# X2C_DC_SHIELD_REVB.net
KiCad netlist of a schematic drawn in EAGLE
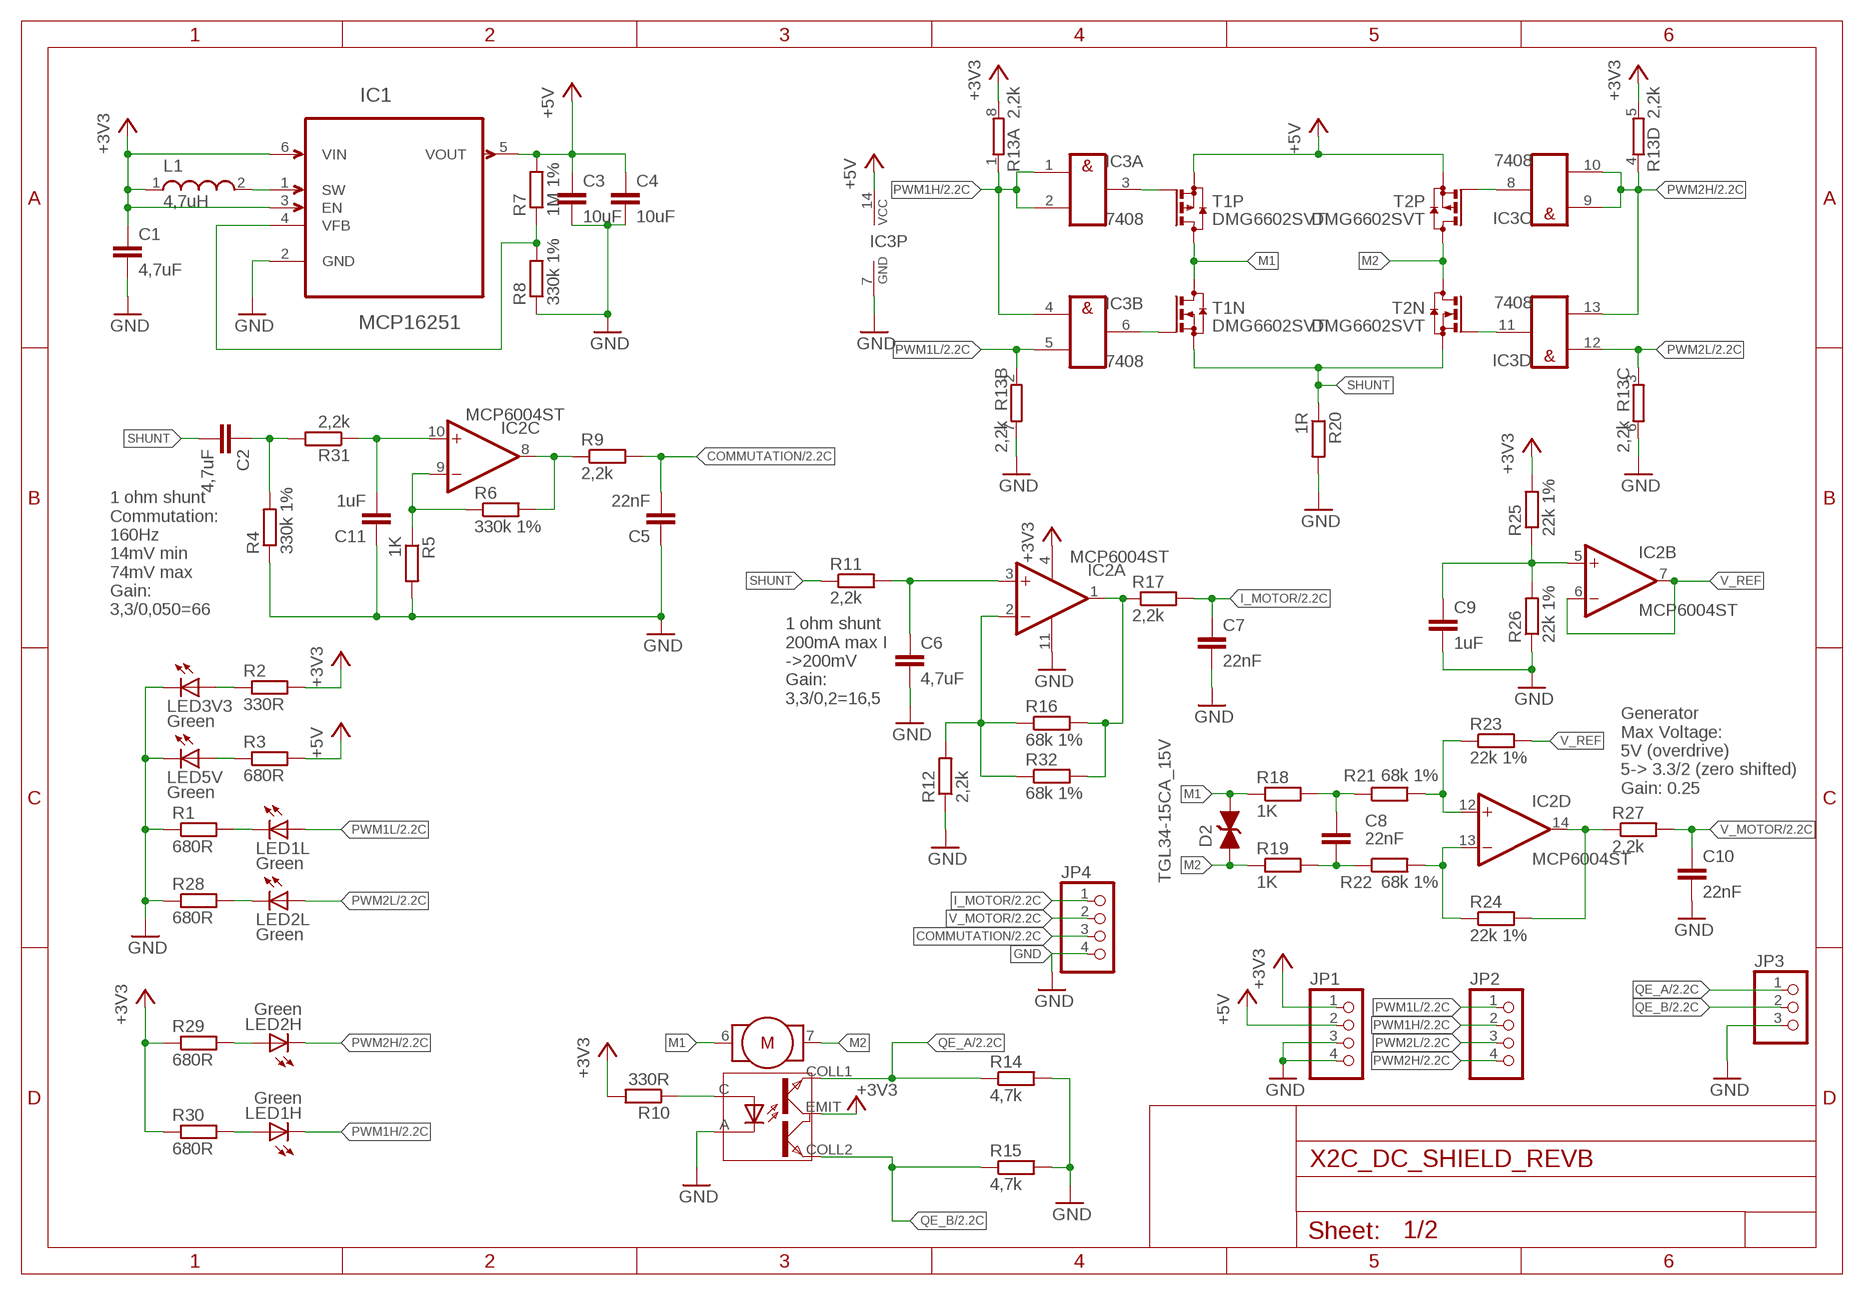
[diagram p0: schematic, sheet 1]
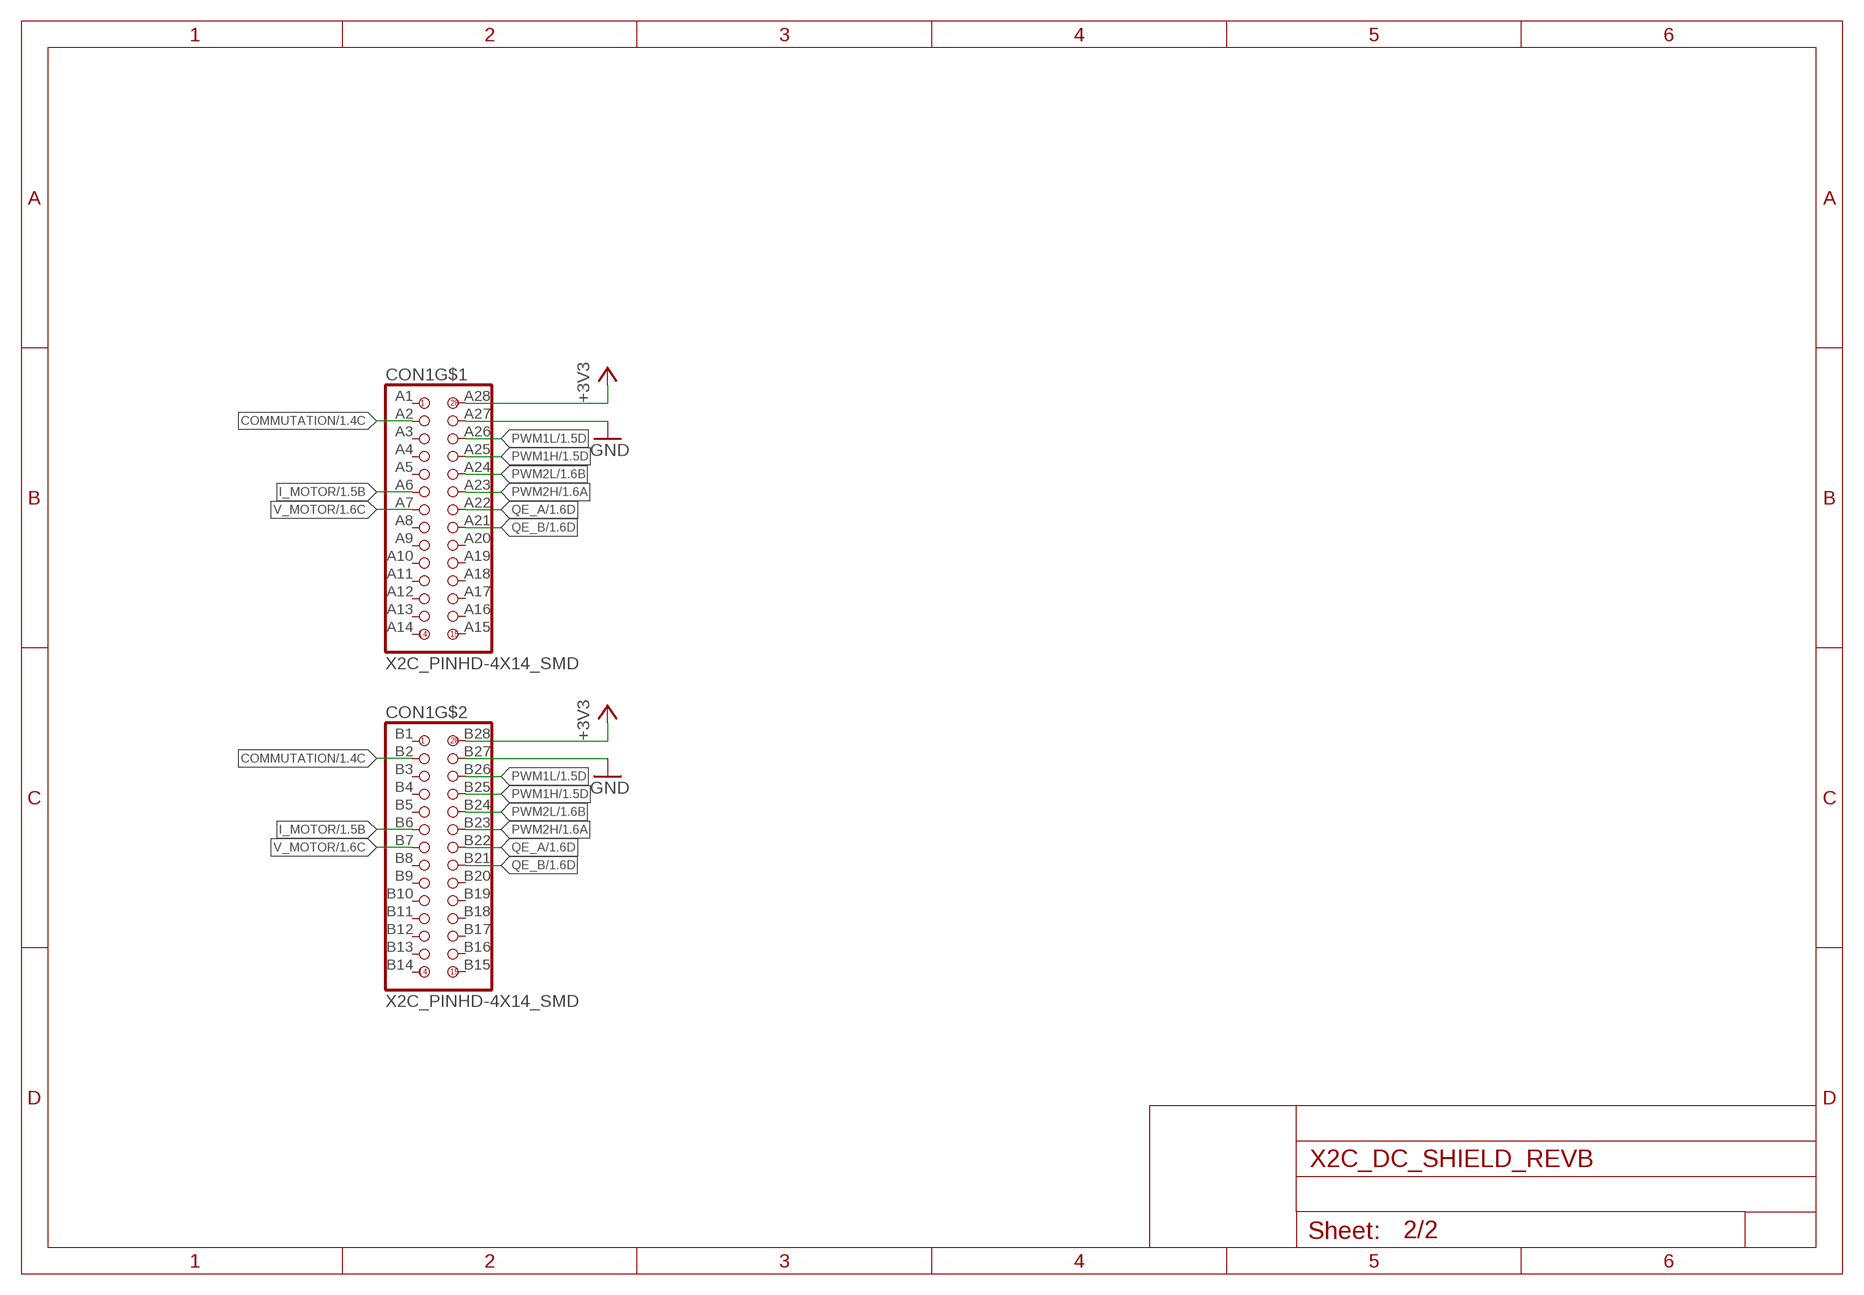
[diagram p1: schematic, sheet 2]

(export (version "E")
  (design (tool "Eeschema 10.0.6"))
  (components
    (comp (ref "C1")
      (value "4,7uF")
      (footprint "eagle-import:C0603K")
      (libsource (lib "eagle-import") (part "KANDO_KOZOS_C-EU-SMD_0603_4,7UF_16V"))
    )
    (comp (ref "C2")
      (value "4,7uF")
      (footprint "eagle-import:C0603K")
      (libsource (lib "eagle-import") (part "KANDO_KOZOS_C-EU-SMD_0603_4,7UF_16V"))
    )
    (comp (ref "C3")
      (value "10uF")
      (footprint "eagle-import:C0805K")
      (libsource (lib "eagle-import") (part "KANDO_KOZOS_C-EU-SMD_0805_10UF_16V"))
    )
    (comp (ref "C4")
      (value "10uF")
      (footprint "eagle-import:C0805K")
      (libsource (lib "eagle-import") (part "C-EU-SMD_0805_10UF_16V"))
    )
    (comp (ref "C5")
      (value "22nF")
      (footprint "eagle-import:C0603K")
      (libsource (lib "eagle-import") (part "C-EU-SMD_0603_22NF_16V"))
    )
    (comp (ref "C6")
      (value "4,7uF")
      (footprint "eagle-import:C0603K")
      (libsource (lib "eagle-import") (part "C-EU-SMD_0603_4,7UF_16V"))
    )
    (comp (ref "C7")
      (value "22nF")
      (footprint "eagle-import:C0603K")
      (libsource (lib "eagle-import") (part "C-EU-SMD_0603_22NF_16V"))
    )
    (comp (ref "C8")
      (value "22nF")
      (footprint "eagle-import:C0603K")
      (libsource (lib "eagle-import") (part "C-EU-SMD_0603_22NF_16V"))
    )
    (comp (ref "C9")
      (value "1uF")
      (footprint "eagle-import:C0603K")
      (libsource (lib "eagle-import") (part "C-EU-SMD_0603_1UF_10V"))
    )
    (comp (ref "C10")
      (value "22nF")
      (footprint "eagle-import:C0603K")
      (libsource (lib "eagle-import") (part "C-EU-SMD_0603_22NF_16V"))
    )
    (comp (ref "C11")
      (value "1uF")
      (footprint "eagle-import:C0603K")
      (libsource (lib "eagle-import") (part "KANDO_KOZOS_V2_C-EU-SMD_0603_1UF_10V"))
    )
    (comp (ref "D2")
      (value "TGL34-15CA_15V")
      (footprint "eagle-import:DO213AA")
      (libsource (lib "eagle-import") (part "TRANSIL_DUAL_DIODE"))
    )
    (comp (ref "IC1")
      (value "MCP16251")
      (footprint "eagle-import:SOT95P270X145-6N")
      (libsource (lib "eagle-import") (part "MCP16251"))
    )
    (comp (ref "IC2")
      (value "MCP6004ST")
      (footprint "eagle-import:TSSOP14")
      (libsource (lib "eagle-import") (part "MCP6004ST"))
    )
    (comp (ref "IC3")
      (value "7408")
      (footprint "eagle-import:TSSOP14")
      (libsource (lib "eagle-import") (part "7408"))
    )
    (comp (ref "JP1")
      (value "PINHD-1X4")
      (footprint "eagle-import:1X04")
      (libsource (lib "eagle-import") (part "PINHD-1X4"))
    )
    (comp (ref "JP2")
      (value "PINHD-1X4")
      (footprint "eagle-import:1X04")
      (libsource (lib "eagle-import") (part "PINHD-1X4"))
    )
    (comp (ref "JP3")
      (value "PINHD-1X03_2.54")
      (footprint "eagle-import:1X03")
      (libsource (lib "eagle-import") (part "PINHD-1X03_2.54"))
    )
    (comp (ref "JP4")
      (value "PINHD-1X4")
      (footprint "eagle-import:1X04")
      (libsource (lib "eagle-import") (part "PINHD-1X4"))
    )
    (comp (ref "L1")
      (value "4,7uH")
      (footprint "eagle-import:WE-TPC_3816")
      (libsource (lib "eagle-import") (part "WE-TPC_3816_4,7UH_0,9A"))
    )
    (comp (ref "LED1H")
      (value "Green")
      (footprint "eagle-import:CHIPLED_0805")
      (libsource (lib "eagle-import") (part "LEDCHIPLED_0805_GREEN"))
    )
    (comp (ref "LED1L")
      (value "Green")
      (footprint "eagle-import:CHIPLED_0805")
      (libsource (lib "eagle-import") (part "LEDCHIPLED_0805_GREEN"))
    )
    (comp (ref "LED2H")
      (value "Green")
      (footprint "eagle-import:CHIPLED_0805")
      (libsource (lib "eagle-import") (part "LEDCHIPLED_0805_GREEN"))
    )
    (comp (ref "LED2L")
      (value "Green")
      (footprint "eagle-import:CHIPLED_0805")
      (libsource (lib "eagle-import") (part "LEDCHIPLED_0805_GREEN"))
    )
    (comp (ref "LED3V3")
      (value "Green")
      (footprint "eagle-import:CHIPLED_0805")
      (libsource (lib "eagle-import") (part "LEDCHIPLED_0805_GREEN"))
    )
    (comp (ref "LED5V")
      (value "Green")
      (footprint "eagle-import:CHIPLED_0805")
      (libsource (lib "eagle-import") (part "LEDCHIPLED_0805_GREEN"))
    )
    (comp (ref "MOT1")
      (value "DC_MOT")
      (footprint "eagle-import:DC_MOTOR")
      (libsource (lib "eagle-import") (part "DC_MOTOR_1"))
    )
    (comp (ref "R1")
      (value "680R")
      (footprint "eagle-import:R0603")
      (libsource (lib "eagle-import") (part "R-EU_SMDR0603_680R"))
    )
    (comp (ref "R2")
      (value "330R")
      (footprint "eagle-import:R0603")
      (libsource (lib "eagle-import") (part "R-EU_SMDR0603_330R"))
    )
    (comp (ref "R3")
      (value "680R")
      (footprint "eagle-import:R0603")
      (libsource (lib "eagle-import") (part "R-EU_SMDR0603_680R"))
    )
    (comp (ref "R4")
      (value "330k 1%")
      (footprint "eagle-import:R0603")
      (libsource (lib "eagle-import") (part "KANDO_KOZOS_V2_R-EU_SMDR0603_330K_1%"))
    )
    (comp (ref "R5")
      (value "1K")
      (footprint "eagle-import:R0603")
      (libsource (lib "eagle-import") (part "R-EU_SMDR0603_1K_1%"))
    )
    (comp (ref "R6")
      (value "330k 1%")
      (footprint "eagle-import:R0603")
      (libsource (lib "eagle-import") (part "KANDO_KOZOS_V2_R-EU_SMDR0603_330K_1%"))
    )
    (comp (ref "R7")
      (value "1M 1%")
      (footprint "eagle-import:R0603")
      (libsource (lib "eagle-import") (part "R-EU_SMDR0603_1M_1%"))
    )
    (comp (ref "R8")
      (value "330k 1%")
      (footprint "eagle-import:R0603")
      (libsource (lib "eagle-import") (part "R-EU_SMDR0603_330K_1%"))
    )
    (comp (ref "R9")
      (value "2,2k")
      (footprint "eagle-import:R0603")
      (libsource (lib "eagle-import") (part "R-EU_SMDR0603_2,2K"))
    )
    (comp (ref "R10")
      (value "330R")
      (footprint "eagle-import:R0603")
      (libsource (lib "eagle-import") (part "R-EU_SMDR0603_330R"))
    )
    (comp (ref "R11")
      (value "2,2k")
      (footprint "eagle-import:R0603")
      (libsource (lib "eagle-import") (part "R-EU_SMDR0603_2,2K"))
    )
    (comp (ref "R12")
      (value "2,2k")
      (footprint "eagle-import:R0603")
      (libsource (lib "eagle-import") (part "R-EU_SMDR0603_2,2K"))
    )
    (comp (ref "R13")
      (value "2,2k")
      (footprint "eagle-import:EXBV8V_A")
      (libsource (lib "eagle-import") (part "4R-N2,2K"))
    )
    (comp (ref "R14")
      (value "4,7k")
      (footprint "eagle-import:R0603")
      (libsource (lib "eagle-import") (part "R-EU_SMDR0603_4,7K"))
    )
    (comp (ref "R15")
      (value "4,7k")
      (footprint "eagle-import:R0603")
      (libsource (lib "eagle-import") (part "R-EU_SMDR0603_4,7K"))
    )
    (comp (ref "R16")
      (value "68k 1%")
      (footprint "eagle-import:R0603")
      (libsource (lib "eagle-import") (part "KANDO_KOZOS_V2_R-EU_SMDR0603_68K_1%"))
    )
    (comp (ref "R17")
      (value "2,2k")
      (footprint "eagle-import:R0603")
      (libsource (lib "eagle-import") (part "R-EU_SMDR0603_2,2K"))
    )
    (comp (ref "R18")
      (value "1K")
      (footprint "eagle-import:R0603")
      (libsource (lib "eagle-import") (part "R-EU_SMDR0603_1K_1%"))
    )
    (comp (ref "R19")
      (value "1K")
      (footprint "eagle-import:R0603")
      (libsource (lib "eagle-import") (part "R-EU_SMDR0603_1K_1%"))
    )
    (comp (ref "R20")
      (value "1R")
      (footprint "eagle-import:R0805")
      (libsource (lib "eagle-import") (part "R-EU_SMDR0805_1R_1%"))
    )
    (comp (ref "R21")
      (value "68k 1%")
      (footprint "eagle-import:R0603")
      (libsource (lib "eagle-import") (part "KANDO_KOZOS_V2_R-EU_SMDR0603_68K_1%"))
    )
    (comp (ref "R22")
      (value "68k 1%")
      (footprint "eagle-import:R0603")
      (libsource (lib "eagle-import") (part "KANDO_KOZOS_V2_R-EU_SMDR0603_68K_1%"))
    )
    (comp (ref "R23")
      (value "22k 1%")
      (footprint "eagle-import:R0603")
      (libsource (lib "eagle-import") (part "KANDO_KOZOS_V2_R-EU_SMDR0603_22K_1%"))
    )
    (comp (ref "R24")
      (value "22k 1%")
      (footprint "eagle-import:R0603")
      (libsource (lib "eagle-import") (part "KANDO_KOZOS_V2_R-EU_SMDR0603_22K_1%"))
    )
    (comp (ref "R25")
      (value "22k 1%")
      (footprint "eagle-import:R0603")
      (libsource (lib "eagle-import") (part "R-EU_SMDR0603_22K_1%"))
    )
    (comp (ref "R26")
      (value "22k 1%")
      (footprint "eagle-import:R0603")
      (libsource (lib "eagle-import") (part "R-EU_SMDR0603_22K_1%"))
    )
    (comp (ref "R27")
      (value "2,2k")
      (footprint "eagle-import:R0603")
      (libsource (lib "eagle-import") (part "R-EU_SMDR0603_2,2K"))
    )
    (comp (ref "R28")
      (value "680R")
      (footprint "eagle-import:R0603")
      (libsource (lib "eagle-import") (part "R-EU_SMDR0603_680R"))
    )
    (comp (ref "R29")
      (value "680R")
      (footprint "eagle-import:R0603")
      (libsource (lib "eagle-import") (part "R-EU_SMDR0603_680R"))
    )
    (comp (ref "R30")
      (value "680R")
      (footprint "eagle-import:R0603")
      (libsource (lib "eagle-import") (part "R-EU_SMDR0603_680R"))
    )
    (comp (ref "R31")
      (value "2,2k")
      (footprint "eagle-import:R0603")
      (libsource (lib "eagle-import") (part "R-EU_SMDR0603_2,2K"))
    )
    (comp (ref "R32")
      (value "68k 1%")
      (footprint "eagle-import:R0603")
      (libsource (lib "eagle-import") (part "KANDO_KOZOS_V2_R-EU_SMDR0603_68K_1%"))
    )
    (comp (ref "T1")
      (value "DMG6602SVT")
      (footprint "eagle-import:TSOT23-6")
      (libsource (lib "eagle-import") (part "DMG6602SVT"))
    )
    (comp (ref "T2")
      (value "DMG6602SVT")
      (footprint "eagle-import:TSOT23-6")
      (libsource (lib "eagle-import") (part "DMG6602SVT"))
    )
    (comp (ref "CON1")
      (value "X2C_PINHD-4X14_SMD")
      (footprint "eagle-import:X2C_4X14_SMD")
      (libsource (lib "eagle-import") (part "X2C_PINHD-4X14_SMD"))
    )
  )
  (nets
    (net (code "1") (name "+3V3") (class "Default")
      (node (ref "C1") (pin "1") (pinfunction "1_1") (pintype "passive"))
      (node (ref "CON1") (pin "A28") (pinfunction "A28_A28") (pintype "passive"))
      (node (ref "CON1") (pin "B28") (pinfunction "A28_B28") (pintype "passive"))
      (node (ref "IC1") (pin "3") (pinfunction "EN_3") (pintype "input"))
      (node (ref "IC1") (pin "6") (pinfunction "VIN_6") (pintype "input"))
      (node (ref "IC2") (pin "4") (pinfunction "V+_4") (pintype "power_in"))
      (node (ref "JP1") (pin "1") (pinfunction "1_1") (pintype "passive"))
      (node (ref "L1") (pin "1") (pinfunction "1_1") (pintype "passive"))
      (node (ref "MOT1") (pin "EMIT") (pinfunction "EMIT_EMIT") (pintype "passive"))
      (node (ref "R10") (pin "2") (pinfunction "2_2") (pintype "passive"))
      (node (ref "R13") (pin "5") (pinfunction "2_5") (pintype "passive"))
      (node (ref "R13") (pin "8") (pinfunction "2_8") (pintype "passive"))
      (node (ref "R2") (pin "2") (pinfunction "2_2") (pintype "passive"))
      (node (ref "R25") (pin "2") (pinfunction "2_2") (pintype "passive"))
      (node (ref "R29") (pin "1") (pinfunction "1_1") (pintype "passive"))
      (node (ref "R30") (pin "1") (pinfunction "1_1") (pintype "passive"))
    )
    (net (code "2") (name "+5V") (class "Default")
      (node (ref "C3") (pin "1") (pinfunction "1_1") (pintype "passive"))
      (node (ref "C4") (pin "1") (pinfunction "1_1") (pintype "passive"))
      (node (ref "IC1") (pin "5") (pinfunction "VOUT_5") (pintype "output"))
      (node (ref "IC3") (pin "14") (pinfunction "VCC_14") (pintype "power_in"))
      (node (ref "JP1") (pin "2") (pinfunction "2_2") (pintype "passive"))
      (node (ref "R3") (pin "2") (pinfunction "2_2") (pintype "passive"))
      (node (ref "R7") (pin "2") (pinfunction "2_2") (pintype "passive"))
      (node (ref "T1") (pin "2") (pinfunction "S_2") (pintype "passive"))
      (node (ref "T2") (pin "2") (pinfunction "S_2") (pintype "passive"))
    )
    (net (code "3") (name "COMMUTATION") (class "Default")
      (node (ref "C5") (pin "2") (pinfunction "2_2") (pintype "passive"))
      (node (ref "CON1") (pin "A2") (pinfunction "A2_A2") (pintype "passive"))
      (node (ref "CON1") (pin "B2") (pinfunction "A2_B2") (pintype "passive"))
      (node (ref "JP4") (pin "3") (pinfunction "3_3") (pintype "passive"))
      (node (ref "R9") (pin "2") (pinfunction "2_2") (pintype "passive"))
    )
    (net (code "4") (name "GND") (class "Default")
      (node (ref "C1") (pin "2") (pinfunction "2_2") (pintype "passive"))
      (node (ref "C10") (pin "2") (pinfunction "2_2") (pintype "passive"))
      (node (ref "C11") (pin "1") (pinfunction "1_1") (pintype "passive"))
      (node (ref "C3") (pin "2") (pinfunction "2_2") (pintype "passive"))
      (node (ref "C4") (pin "2") (pinfunction "2_2") (pintype "passive"))
      (node (ref "C5") (pin "1") (pinfunction "1_1") (pintype "passive"))
      (node (ref "C6") (pin "2") (pinfunction "2_2") (pintype "passive"))
      (node (ref "C7") (pin "2") (pinfunction "2_2") (pintype "passive"))
      (node (ref "C9") (pin "2") (pinfunction "2_2") (pintype "passive"))
      (node (ref "CON1") (pin "A27") (pinfunction "A27_A27") (pintype "passive"))
      (node (ref "CON1") (pin "B27") (pinfunction "A27_B27") (pintype "passive"))
      (node (ref "IC1") (pin "2") (pinfunction "GND_2") (pintype "passive"))
      (node (ref "IC2") (pin "11") (pinfunction "V-_11") (pintype "power_in"))
      (node (ref "IC3") (pin "7") (pinfunction "GND_7") (pintype "power_in"))
      (node (ref "JP1") (pin "3") (pinfunction "3_3") (pintype "passive"))
      (node (ref "JP1") (pin "4") (pinfunction "4_4") (pintype "passive"))
      (node (ref "JP3") (pin "3") (pinfunction "3_3") (pintype "passive"))
      (node (ref "JP4") (pin "4") (pinfunction "4_4") (pintype "passive"))
      (node (ref "LED3V3") (pin "C") (pinfunction "C_C") (pintype "passive"))
      (node (ref "LED5V") (pin "C") (pinfunction "C_C") (pintype "passive"))
      (node (ref "MOT1") (pin "A") (pinfunction "C_A") (pintype "passive"))
      (node (ref "R1") (pin "1") (pinfunction "1_1") (pintype "passive"))
      (node (ref "R12") (pin "1") (pinfunction "1_1") (pintype "passive"))
      (node (ref "R13") (pin "6") (pinfunction "2_6") (pintype "passive"))
      (node (ref "R13") (pin "7") (pinfunction "2_7") (pintype "passive"))
      (node (ref "R14") (pin "2") (pinfunction "2_2") (pintype "passive"))
      (node (ref "R15") (pin "2") (pinfunction "2_2") (pintype "passive"))
      (node (ref "R20") (pin "2") (pinfunction "2_2") (pintype "passive"))
      (node (ref "R26") (pin "1") (pinfunction "1_1") (pintype "passive"))
      (node (ref "R28") (pin "1") (pinfunction "1_1") (pintype "passive"))
      (node (ref "R4") (pin "1") (pinfunction "1_1") (pintype "passive"))
      (node (ref "R5") (pin "2") (pinfunction "2_2") (pintype "passive"))
      (node (ref "R8") (pin "1") (pinfunction "1_1") (pintype "passive"))
    )
    (net (code "5") (name "I_MOTOR") (class "Default")
      (node (ref "C7") (pin "1") (pinfunction "1_1") (pintype "passive"))
      (node (ref "CON1") (pin "A6") (pinfunction "A6_A6") (pintype "passive"))
      (node (ref "CON1") (pin "B6") (pinfunction "A6_B6") (pintype "passive"))
      (node (ref "JP4") (pin "1") (pinfunction "1_1") (pintype "passive"))
      (node (ref "R17") (pin "2") (pinfunction "2_2") (pintype "passive"))
    )
    (net (code "6") (name "M1") (class "Default")
      (node (ref "D2") (pin "C") (pinfunction "P$2_C") (pintype "bidirectional"))
      (node (ref "MOT1") (pin "6") (pinfunction "MOT1_6") (pintype "passive"))
      (node (ref "R18") (pin "1") (pinfunction "1_1") (pintype "passive"))
      (node (ref "T1") (pin "4") (pinfunction "D_4") (pintype "passive"))
      (node (ref "T1") (pin "6") (pinfunction "D_6") (pintype "passive"))
    )
    (net (code "7") (name "M2") (class "Default")
      (node (ref "D2") (pin "A") (pinfunction "P$1_A") (pintype "bidirectional"))
      (node (ref "MOT1") (pin "7") (pinfunction "MOT2_7") (pintype "passive"))
      (node (ref "R19") (pin "1") (pinfunction "1_1") (pintype "passive"))
      (node (ref "T2") (pin "4") (pinfunction "D_4") (pintype "passive"))
      (node (ref "T2") (pin "6") (pinfunction "D_6") (pintype "passive"))
    )
    (net (code "8") (name "Net-(C2-Pad1)") (class "Default")
      (node (ref "C2") (pin "1") (pinfunction "1_1") (pintype "passive"))
      (node (ref "R31") (pin "2") (pinfunction "2_2") (pintype "passive"))
      (node (ref "R4") (pin "2") (pinfunction "2_2") (pintype "passive"))
    )
    (net (code "9") (name "Net-(C8-Pad1)") (class "Default")
      (node (ref "C8") (pin "1") (pinfunction "1_1") (pintype "passive"))
      (node (ref "R18") (pin "2") (pinfunction "2_2") (pintype "passive"))
      (node (ref "R21") (pin "1") (pinfunction "1_1") (pintype "passive"))
    )
    (net (code "10") (name "Net-(C8-Pad2)") (class "Default")
      (node (ref "C8") (pin "2") (pinfunction "2_2") (pintype "passive"))
      (node (ref "R19") (pin "2") (pinfunction "2_2") (pintype "passive"))
      (node (ref "R22") (pin "1") (pinfunction "1_1") (pintype "passive"))
    )
    (net (code "11") (name "Net-(IC1-SW)") (class "Default")
      (node (ref "IC1") (pin "1") (pinfunction "SW_1") (pintype "input"))
      (node (ref "L1") (pin "2") (pinfunction "2_2") (pintype "passive"))
    )
    (net (code "12") (name "Net-(IC1-VFB)") (class "Default")
      (node (ref "IC1") (pin "4") (pinfunction "VFB_4") (pintype "input"))
      (node (ref "R7") (pin "1") (pinfunction "1_1") (pintype "passive"))
      (node (ref "R8") (pin "2") (pinfunction "2_2") (pintype "passive"))
    )
    (net (code "13") (name "Net-(IC2A-+IN)") (class "Default")
      (node (ref "C6") (pin "1") (pinfunction "1_1") (pintype "passive"))
      (node (ref "IC2") (pin "3") (pinfunction "+IN_3") (pintype "input"))
      (node (ref "R11") (pin "2") (pinfunction "2_2") (pintype "passive"))
    )
    (net (code "14") (name "Net-(IC2A--IN)") (class "Default")
      (node (ref "IC2") (pin "2") (pinfunction "-IN_2") (pintype "input"))
      (node (ref "R12") (pin "2") (pinfunction "2_2") (pintype "passive"))
      (node (ref "R16") (pin "1") (pinfunction "1_1") (pintype "passive"))
      (node (ref "R32") (pin "1") (pinfunction "1_1") (pintype "passive"))
    )
    (net (code "15") (name "Net-(IC2A-OUT)") (class "Default")
      (node (ref "IC2") (pin "1") (pinfunction "OUT_1") (pintype "output"))
      (node (ref "R16") (pin "2") (pinfunction "2_2") (pintype "passive"))
      (node (ref "R17") (pin "1") (pinfunction "1_1") (pintype "passive"))
      (node (ref "R32") (pin "2") (pinfunction "2_2") (pintype "passive"))
    )
    (net (code "16") (name "Net-(IC2B-+IN)") (class "Default")
      (node (ref "C9") (pin "1") (pinfunction "1_1") (pintype "passive"))
      (node (ref "IC2") (pin "5") (pinfunction "+IN_5") (pintype "input"))
      (node (ref "R25") (pin "1") (pinfunction "1_1") (pintype "passive"))
      (node (ref "R26") (pin "2") (pinfunction "2_2") (pintype "passive"))
    )
    (net (code "17") (name "Net-(IC2C-+IN)") (class "Default")
      (node (ref "C11") (pin "2") (pinfunction "2_2") (pintype "passive"))
      (node (ref "IC2") (pin "10") (pinfunction "+IN_10") (pintype "input"))
      (node (ref "R31") (pin "1") (pinfunction "1_1") (pintype "passive"))
    )
    (net (code "18") (name "Net-(IC2C--IN)") (class "Default")
      (node (ref "IC2") (pin "9") (pinfunction "-IN_9") (pintype "input"))
      (node (ref "R5") (pin "1") (pinfunction "1_1") (pintype "passive"))
      (node (ref "R6") (pin "1") (pinfunction "1_1") (pintype "passive"))
    )
    (net (code "19") (name "Net-(IC2C-OUT)") (class "Default")
      (node (ref "IC2") (pin "8") (pinfunction "OUT_8") (pintype "output"))
      (node (ref "R6") (pin "2") (pinfunction "2_2") (pintype "passive"))
      (node (ref "R9") (pin "1") (pinfunction "1_1") (pintype "passive"))
    )
    (net (code "20") (name "Net-(IC2D-+IN)") (class "Default")
      (node (ref "IC2") (pin "12") (pinfunction "+IN_12") (pintype "input"))
      (node (ref "R21") (pin "2") (pinfunction "2_2") (pintype "passive"))
      (node (ref "R23") (pin "1") (pinfunction "1_1") (pintype "passive"))
    )
    (net (code "21") (name "Net-(IC2D--IN)") (class "Default")
      (node (ref "IC2") (pin "13") (pinfunction "-IN_13") (pintype "input"))
      (node (ref "R22") (pin "2") (pinfunction "2_2") (pintype "passive"))
      (node (ref "R24") (pin "1") (pinfunction "1_1") (pintype "passive"))
    )
    (net (code "22") (name "Net-(IC2D-OUT)") (class "Default")
      (node (ref "IC2") (pin "14") (pinfunction "OUT_14") (pintype "output"))
      (node (ref "R24") (pin "2") (pinfunction "2_2") (pintype "passive"))
      (node (ref "R27") (pin "1") (pinfunction "1_1") (pintype "passive"))
    )
    (net (code "23") (name "Net-(IC3A-O)") (class "Default")
      (node (ref "IC3") (pin "3") (pinfunction "O_3") (pintype "output"))
      (node (ref "T1") (pin "3") (pinfunction "G_3") (pintype "passive"))
    )
    (net (code "24") (name "Net-(IC3B-O)") (class "Default")
      (node (ref "IC3") (pin "6") (pinfunction "O_6") (pintype "output"))
      (node (ref "T1") (pin "1") (pinfunction "G_1") (pintype "passive"))
    )
    (net (code "25") (name "Net-(IC3C-O)") (class "Default")
      (node (ref "IC3") (pin "8") (pinfunction "O_8") (pintype "output"))
      (node (ref "T2") (pin "3") (pinfunction "G_3") (pintype "passive"))
    )
    (net (code "26") (name "Net-(IC3D-O)") (class "Default")
      (node (ref "IC3") (pin "11") (pinfunction "O_11") (pintype "output"))
      (node (ref "T2") (pin "1") (pinfunction "G_1") (pintype "passive"))
    )
    (net (code "27") (name "Net-(LED1H-PadA)") (class "Default")
      (node (ref "LED1H") (pin "A") (pinfunction "A_A") (pintype "passive"))
      (node (ref "R30") (pin "2") (pinfunction "2_2") (pintype "passive"))
    )
    (net (code "28") (name "Net-(LED1L-PadC)") (class "Default")
      (node (ref "LED1L") (pin "C") (pinfunction "C_C") (pintype "passive"))
      (node (ref "R1") (pin "2") (pinfunction "2_2") (pintype "passive"))
    )
    (net (code "29") (name "Net-(LED2H-PadA)") (class "Default")
      (node (ref "LED2H") (pin "A") (pinfunction "A_A") (pintype "passive"))
      (node (ref "R29") (pin "2") (pinfunction "2_2") (pintype "passive"))
    )
    (net (code "30") (name "Net-(LED2L-PadC)") (class "Default")
      (node (ref "LED2L") (pin "C") (pinfunction "C_C") (pintype "passive"))
      (node (ref "R28") (pin "2") (pinfunction "2_2") (pintype "passive"))
    )
    (net (code "31") (name "Net-(LED3V3-PadA)") (class "Default")
      (node (ref "LED3V3") (pin "A") (pinfunction "A_A") (pintype "passive"))
      (node (ref "R2") (pin "1") (pinfunction "1_1") (pintype "passive"))
    )
    (net (code "32") (name "Net-(LED5V-PadA)") (class "Default")
      (node (ref "LED5V") (pin "A") (pinfunction "A_A") (pintype "passive"))
      (node (ref "R3") (pin "1") (pinfunction "1_1") (pintype "passive"))
    )
    (net (code "33") (name "Net-(MOT1-A)") (class "Default")
      (node (ref "MOT1") (pin "C") (pinfunction "A_C") (pintype "passive"))
      (node (ref "R10") (pin "1") (pinfunction "1_1") (pintype "passive"))
    )
    (net (code "34") (name "PWM1H") (class "Default")
      (node (ref "CON1") (pin "A25") (pinfunction "A25_A25") (pintype "passive"))
      (node (ref "CON1") (pin "B25") (pinfunction "A25_B25") (pintype "passive"))
      (node (ref "IC3") (pin "1") (pinfunction "I0_1") (pintype "input"))
      (node (ref "IC3") (pin "2") (pinfunction "I1_2") (pintype "input"))
      (node (ref "IC3") (pin "4") (pinfunction "I0_4") (pintype "input"))
      (node (ref "JP2") (pin "2") (pinfunction "2_2") (pintype "passive"))
      (node (ref "LED1H") (pin "C") (pinfunction "C_C") (pintype "passive"))
      (node (ref "R13") (pin "1") (pinfunction "1_1") (pintype "passive"))
    )
    (net (code "35") (name "PWM1L") (class "Default")
      (node (ref "CON1") (pin "A26") (pinfunction "A26_A26") (pintype "passive"))
      (node (ref "CON1") (pin "B26") (pinfunction "A26_B26") (pintype "passive"))
      (node (ref "IC3") (pin "5") (pinfunction "I1_5") (pintype "input"))
      (node (ref "JP2") (pin "1") (pinfunction "1_1") (pintype "passive"))
      (node (ref "LED1L") (pin "A") (pinfunction "A_A") (pintype "passive"))
      (node (ref "R13") (pin "2") (pinfunction "1_2") (pintype "passive"))
    )
    (net (code "36") (name "PWM2H") (class "Default")
      (node (ref "CON1") (pin "A23") (pinfunction "A23_A23") (pintype "passive"))
      (node (ref "CON1") (pin "B23") (pinfunction "A23_B23") (pintype "passive"))
      (node (ref "IC3") (pin "10") (pinfunction "I1_10") (pintype "input"))
      (node (ref "IC3") (pin "13") (pinfunction "I1_13") (pintype "input"))
      (node (ref "IC3") (pin "9") (pinfunction "I0_9") (pintype "input"))
      (node (ref "JP2") (pin "4") (pinfunction "4_4") (pintype "passive"))
      (node (ref "LED2H") (pin "C") (pinfunction "C_C") (pintype "passive"))
      (node (ref "R13") (pin "4") (pinfunction "1_4") (pintype "passive"))
    )
    (net (code "37") (name "PWM2L") (class "Default")
      (node (ref "CON1") (pin "A24") (pinfunction "A24_A24") (pintype "passive"))
      (node (ref "CON1") (pin "B24") (pinfunction "A24_B24") (pintype "passive"))
      (node (ref "IC3") (pin "12") (pinfunction "I0_12") (pintype "input"))
      (node (ref "JP2") (pin "3") (pinfunction "3_3") (pintype "passive"))
      (node (ref "LED2L") (pin "A") (pinfunction "A_A") (pintype "passive"))
      (node (ref "R13") (pin "3") (pinfunction "1_3") (pintype "passive"))
    )
    (net (code "38") (name "QE_A") (class "Default")
      (node (ref "CON1") (pin "A22") (pinfunction "A22_A22") (pintype "passive"))
      (node (ref "CON1") (pin "B22") (pinfunction "A22_B22") (pintype "passive"))
      (node (ref "JP3") (pin "1") (pinfunction "1_1") (pintype "passive"))
      (node (ref "MOT1") (pin "COLL1") (pinfunction "COL1_COLL1") (pintype "passive"))
      (node (ref "R14") (pin "1") (pinfunction "1_1") (pintype "passive"))
    )
    (net (code "39") (name "QE_B") (class "Default")
      (node (ref "CON1") (pin "A21") (pinfunction "A21_A21") (pintype "passive"))
      (node (ref "CON1") (pin "B21") (pinfunction "A21_B21") (pintype "passive"))
      (node (ref "JP3") (pin "2") (pinfunction "2_2") (pintype "passive"))
      (node (ref "MOT1") (pin "COLL2") (pinfunction "COL2_COLL2") (pintype "passive"))
      (node (ref "R15") (pin "1") (pinfunction "1_1") (pintype "passive"))
    )
    (net (code "40") (name "SHUNT") (class "Default")
      (node (ref "C2") (pin "2") (pinfunction "2_2") (pintype "passive"))
      (node (ref "R11") (pin "1") (pinfunction "1_1") (pintype "passive"))
      (node (ref "R20") (pin "1") (pinfunction "1_1") (pintype "passive"))
      (node (ref "T1") (pin "5") (pinfunction "S_5") (pintype "passive"))
      (node (ref "T2") (pin "5") (pinfunction "S_5") (pintype "passive"))
    )
    (net (code "41") (name "V_MOTOR") (class "Default")
      (node (ref "C10") (pin "1") (pinfunction "1_1") (pintype "passive"))
      (node (ref "CON1") (pin "A7") (pinfunction "A7_A7") (pintype "passive"))
      (node (ref "CON1") (pin "B7") (pinfunction "A7_B7") (pintype "passive"))
      (node (ref "JP4") (pin "2") (pinfunction "2_2") (pintype "passive"))
      (node (ref "R27") (pin "2") (pinfunction "2_2") (pintype "passive"))
    )
    (net (code "42") (name "V_REF") (class "Default")
      (node (ref "IC2") (pin "6") (pinfunction "-IN_6") (pintype "input"))
      (node (ref "IC2") (pin "7") (pinfunction "OUT_7") (pintype "output"))
      (node (ref "R23") (pin "2") (pinfunction "2_2") (pintype "passive"))
    )
    (net (code "43") (name "unconnected-(CON1-PadA1)") (class "Default")
      (node (ref "CON1") (pin "A1") (pinfunction "A1_A1") (pintype "passive"))
    )
    (net (code "44") (name "unconnected-(CON1-PadA3)") (class "Default")
      (node (ref "CON1") (pin "A3") (pinfunction "A3_A3") (pintype "passive"))
    )
    (net (code "45") (name "unconnected-(CON1-PadA4)") (class "Default")
      (node (ref "CON1") (pin "A4") (pinfunction "A4_A4") (pintype "passive"))
    )
    (net (code "46") (name "unconnected-(CON1-PadA5)") (class "Default")
      (node (ref "CON1") (pin "A5") (pinfunction "A5_A5") (pintype "passive"))
    )
    (net (code "47") (name "unconnected-(CON1-PadA8)") (class "Default")
      (node (ref "CON1") (pin "A8") (pinfunction "A8_A8") (pintype "passive"))
    )
    (net (code "48") (name "unconnected-(CON1-PadA9)") (class "Default")
      (node (ref "CON1") (pin "A9") (pinfunction "A9_A9") (pintype "passive"))
    )
    (net (code "49") (name "unconnected-(CON1-PadA10)") (class "Default")
      (node (ref "CON1") (pin "A10") (pinfunction "A10_A10") (pintype "passive"))
    )
    (net (code "50") (name "unconnected-(CON1-PadA11)") (class "Default")
      (node (ref "CON1") (pin "A11") (pinfunction "A11_A11") (pintype "passive"))
    )
    (net (code "51") (name "unconnected-(CON1-PadA12)") (class "Default")
      (node (ref "CON1") (pin "A12") (pinfunction "A12_A12") (pintype "passive"))
    )
    (net (code "52") (name "unconnected-(CON1-PadA13)") (class "Default")
      (node (ref "CON1") (pin "A13") (pinfunction "A13_A13") (pintype "passive"))
    )
    (net (code "53") (name "unconnected-(CON1-PadA14)") (class "Default")
      (node (ref "CON1") (pin "A14") (pinfunction "A14_A14") (pintype "passive"))
    )
    (net (code "54") (name "unconnected-(CON1-PadA15)") (class "Default")
      (node (ref "CON1") (pin "A15") (pinfunction "A15_A15") (pintype "passive"))
    )
    (net (code "55") (name "unconnected-(CON1-PadA16)") (class "Default")
      (node (ref "CON1") (pin "A16") (pinfunction "A16_A16") (pintype "passive"))
    )
    (net (code "56") (name "unconnected-(CON1-PadA17)") (class "Default")
      (node (ref "CON1") (pin "A17") (pinfunction "A17_A17") (pintype "passive"))
    )
    (net (code "57") (name "unconnected-(CON1-PadA18)") (class "Default")
      (node (ref "CON1") (pin "A18") (pinfunction "A18_A18") (pintype "passive"))
    )
    (net (code "58") (name "unconnected-(CON1-PadA19)") (class "Default")
      (node (ref "CON1") (pin "A19") (pinfunction "A19_A19") (pintype "passive"))
    )
    (net (code "59") (name "unconnected-(CON1-PadA20)") (class "Default")
      (node (ref "CON1") (pin "A20") (pinfunction "A20_A20") (pintype "passive"))
    )
    (net (code "60") (name "unconnected-(CON1B-A1-PadB1)") (class "Default")
      (node (ref "CON1") (pin "B1") (pinfunction "A1_B1") (pintype "passive"))
    )
    (net (code "61") (name "unconnected-(CON1B-A3-PadB3)") (class "Default")
      (node (ref "CON1") (pin "B3") (pinfunction "A3_B3") (pintype "passive"))
    )
    (net (code "62") (name "unconnected-(CON1B-A4-PadB4)") (class "Default")
      (node (ref "CON1") (pin "B4") (pinfunction "A4_B4") (pintype "passive"))
    )
    (net (code "63") (name "unconnected-(CON1B-A5-PadB5)") (class "Default")
      (node (ref "CON1") (pin "B5") (pinfunction "A5_B5") (pintype "passive"))
    )
    (net (code "64") (name "unconnected-(CON1B-A8-PadB8)") (class "Default")
      (node (ref "CON1") (pin "B8") (pinfunction "A8_B8") (pintype "passive"))
    )
    (net (code "65") (name "unconnected-(CON1B-A9-PadB9)") (class "Default")
      (node (ref "CON1") (pin "B9") (pinfunction "A9_B9") (pintype "passive"))
    )
    (net (code "66") (name "unconnected-(CON1B-A10-PadB10)") (class "Default")
      (node (ref "CON1") (pin "B10") (pinfunction "A10_B10") (pintype "passive"))
    )
    (net (code "67") (name "unconnected-(CON1B-A11-PadB11)") (class "Default")
      (node (ref "CON1") (pin "B11") (pinfunction "A11_B11") (pintype "passive"))
    )
    (net (code "68") (name "unconnected-(CON1B-A12-PadB12)") (class "Default")
      (node (ref "CON1") (pin "B12") (pinfunction "A12_B12") (pintype "passive"))
    )
    (net (code "69") (name "unconnected-(CON1B-A13-PadB13)") (class "Default")
      (node (ref "CON1") (pin "B13") (pinfunction "A13_B13") (pintype "passive"))
    )
    (net (code "70") (name "unconnected-(CON1B-A14-PadB14)") (class "Default")
      (node (ref "CON1") (pin "B14") (pinfunction "A14_B14") (pintype "passive"))
    )
    (net (code "71") (name "unconnected-(CON1B-A15-PadB15)") (class "Default")
      (node (ref "CON1") (pin "B15") (pinfunction "A15_B15") (pintype "passive"))
    )
    (net (code "72") (name "unconnected-(CON1B-A16-PadB16)") (class "Default")
      (node (ref "CON1") (pin "B16") (pinfunction "A16_B16") (pintype "passive"))
    )
    (net (code "73") (name "unconnected-(CON1B-A17-PadB17)") (class "Default")
      (node (ref "CON1") (pin "B17") (pinfunction "A17_B17") (pintype "passive"))
    )
    (net (code "74") (name "unconnected-(CON1B-A18-PadB18)") (class "Default")
      (node (ref "CON1") (pin "B18") (pinfunction "A18_B18") (pintype "passive"))
    )
    (net (code "75") (name "unconnected-(CON1B-A19-PadB19)") (class "Default")
      (node (ref "CON1") (pin "B19") (pinfunction "A19_B19") (pintype "passive"))
    )
    (net (code "76") (name "unconnected-(CON1B-A20-PadB20)") (class "Default")
      (node (ref "CON1") (pin "B20") (pinfunction "A20_B20") (pintype "passive"))
    )
  )
)
